# TEBF0808.net
KiCad netlist of a schematic drawn in Altium Designer
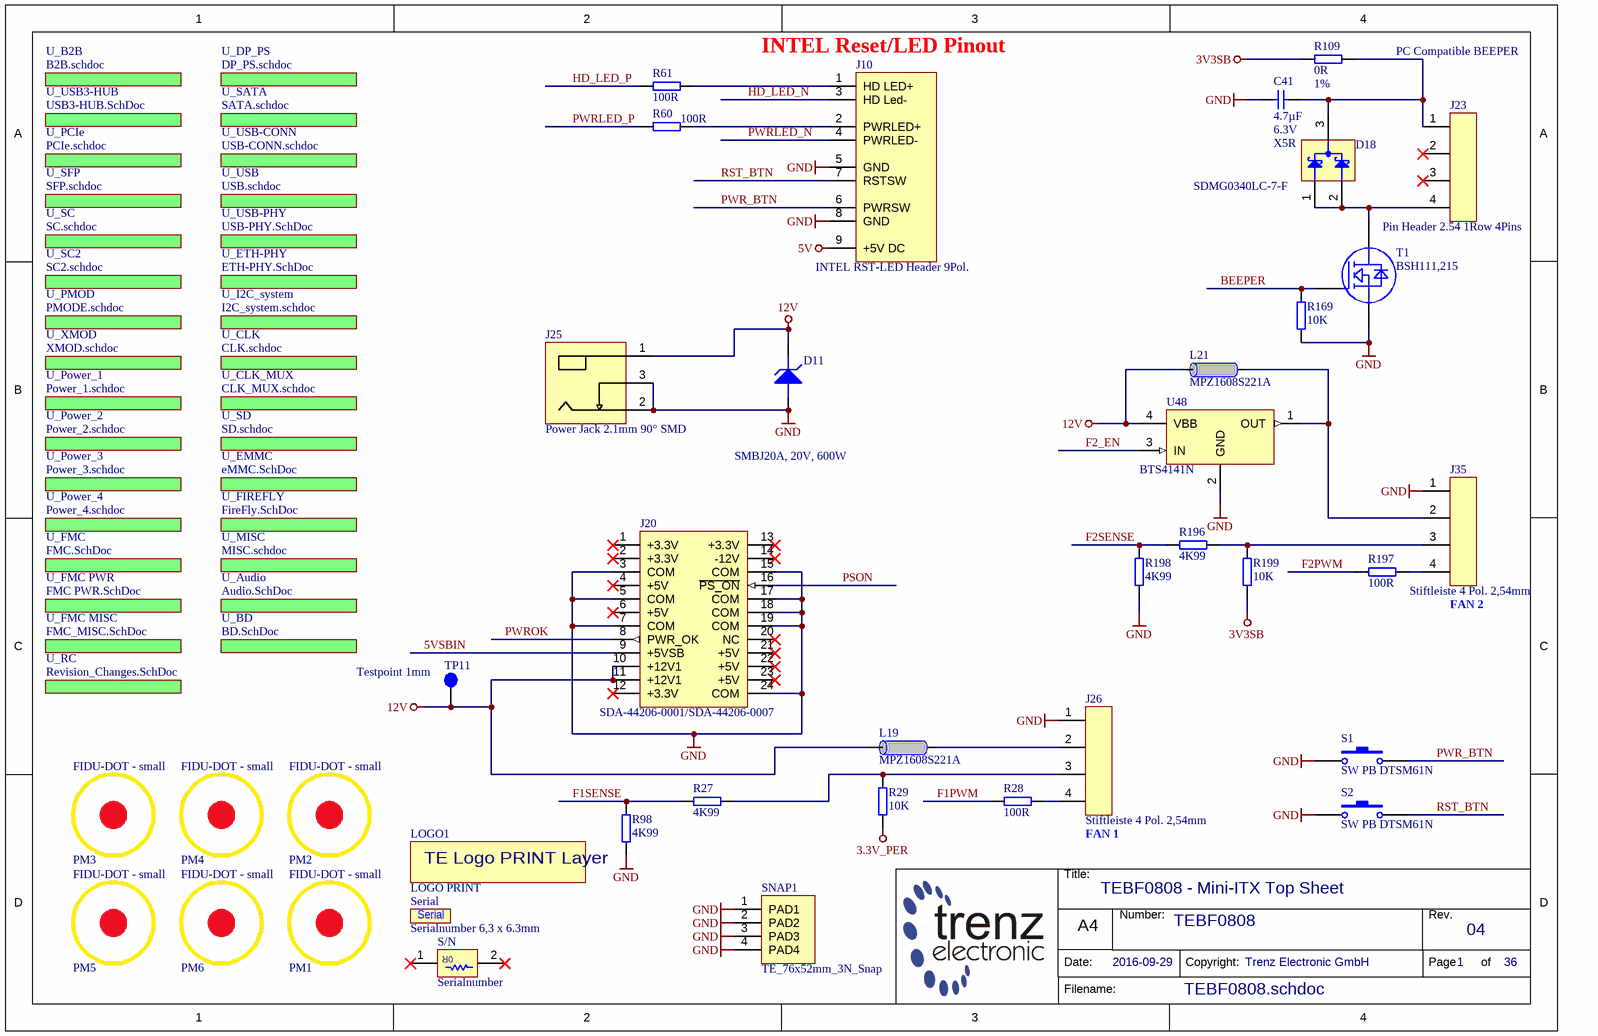
[diagram p0: TEBF0808.schdoc]

(export (version "E")
  (design (tool "Eeschema 10.0.6"))
  (components
    (comp (ref "C41")
      (value "4.7µF")
      (footprint "CAPC1005X60N")
      (description "KON 4.7µF 6.3V X5R SMD 20%")
      (fields
        (field (name "VOLTAGE") "6.3V")
        (field (name "TECHNOLOGY") "X5R")
        (field (name "TOLERANCE") "20%")
      )
      (libsource (lib "TE") (part "CAP-NP"))
    )
    (comp (ref "D11")
      (value "SMBJ20A, 20V, 600W")
      (footprint "DIOM5236X261N")
      (description "TVS, Unidirectional, 20V, 600W")
      (libsource (lib "TE") (part "SUPRESSOR"))
    )
    (comp (ref "D18")
      (value "SDMG0340LC-7-F")
      (footprint "SOT65P210X110-3N")
      (libsource (lib "TE") (part "SDMG0340LC"))
    )
    (comp (ref "J10")
      (value "INTEL RST-LED Header 9Pol.")
      (footprint "INTEL_FP_RST_LED_9PIN")
      (description "Stiftleiste Intel RST-LED Header 9polig")
      (libsource (lib "TE") (part "INTEL_FP_RST_LED_9PIN"))
    )
    (comp (ref "J20")
      (value "SDA-44206-0001/SDA-44206-0007")
      (footprint "SDA-44206-0001")
      (description "ATX Main Connector 24pol.")
      (libsource (lib "TE") (part "ATX-MAIN"))
    )
    (comp (ref "J23")
      (value "Pin Header 2.54 1Row 4Pins")
      (footprint "STIFTLEISTE2_54 OG 1R-4")
      (description "Stiftleiste gerade 1-reihig, 4pol.")
      (libsource (lib "TE") (part "CON-4"))
    )
    (comp (ref "J25")
      (value "Power Jack 2.1mm 90° SMD")
      (footprint "694106106102")
      (libsource (lib "TE") (part "694106106102"))
    )
    (comp (ref "J26")
      (value "Stiftleiste 4 Pol. 2,54mm")
      (footprint "47053-1000")
      (description "Stiftleiste 4 Pol. 7.5mm 2,54mm PC FAN")
      (libsource (lib "TE") (part "CON-4"))
    )
    (comp (ref "J35")
      (value "Stiftleiste 4 Pol. 2,54mm")
      (footprint "47053-1000")
      (description "Stiftleiste 4 Pol. 7.5mm 2,54mm PC FAN")
      (libsource (lib "TE") (part "CON-4"))
    )
    (comp (ref "L19")
      (value "MPZ1608S221A")
      (footprint "INDC1608X95N")
      (description "Ferritdurchführung MPZ1608S221A")
      (libsource (lib "TE") (part "Ferritperle"))
    )
    (comp (ref "L21")
      (value "MPZ1608S221A")
      (footprint "INDC1608X95N")
      (description "Ferritdurchführung MPZ1608S221A")
      (libsource (lib "TE") (part "Ferritperle"))
    )
    (comp (ref "LOGO1")
      (value "LOGO PRINT")
      (footprint "LOGO PRINT")
      (libsource (lib "TE") (part "LOGO PRINT"))
    )
    (comp (ref "PM1")
      (value "FIDU-DOT - small")
      (footprint "FIDU-DOT - small")
      (description "FIDU-DOT - SMALL 1mm")
      (libsource (lib "TE") (part "FIDU-DOT - small"))
    )
    (comp (ref "PM2")
      (value "FIDU-DOT - small")
      (footprint "FIDU-DOT - small")
      (description "FIDU-DOT - SMALL 1mm")
      (libsource (lib "TE") (part "FIDU-DOT - small"))
    )
    (comp (ref "PM3")
      (value "FIDU-DOT - small")
      (footprint "FIDU-DOT - small")
      (description "FIDU-DOT - SMALL 1mm")
      (libsource (lib "TE") (part "FIDU-DOT - small"))
    )
    (comp (ref "PM4")
      (value "FIDU-DOT - small")
      (footprint "FIDU-DOT - small")
      (description "FIDU-DOT - SMALL 1mm")
      (libsource (lib "TE") (part "FIDU-DOT - small"))
    )
    (comp (ref "PM5")
      (value "FIDU-DOT - small")
      (footprint "FIDU-DOT - small")
      (description "FIDU-DOT - SMALL 1mm")
      (libsource (lib "TE") (part "FIDU-DOT - small"))
    )
    (comp (ref "PM6")
      (value "FIDU-DOT - small")
      (footprint "FIDU-DOT - small")
      (description "FIDU-DOT - SMALL 1mm")
      (libsource (lib "TE") (part "FIDU-DOT - small"))
    )
    (comp (ref "R27")
      (value "4K99")
      (footprint "RESC1005X40N")
      (description "WID SMD 4K99 1% 0,063W")
      (fields (field (name "TOLERANCE") "1%"))
      (libsource (lib "TE") (part "RES"))
    )
    (comp (ref "R28")
      (value "100R")
      (footprint "RESC1005X40N")
      (description "WID SMD 100R 1% 0,063W")
      (fields (field (name "TOLERANCE") "1%"))
      (libsource (lib "TE") (part "RES"))
    )
    (comp (ref "R29")
      (value "10K")
      (footprint "RESC1005X40N")
      (description "WID SMD 10K 1% 0,063W")
      (fields (field (name "TOLERANCE") "1%"))
      (libsource (lib "TE") (part "RES"))
    )
    (comp (ref "R60")
      (value "100R")
      (footprint "RESC1005X40N")
      (description "WID SMD 100R 1% 0,063W")
      (fields (field (name "TOLERANCE") "1%"))
      (libsource (lib "TE") (part "RES"))
    )
    (comp (ref "R61")
      (value "100R")
      (footprint "RESC1005X40N")
      (description "WID SMD 100R 1% 0,063W")
      (fields (field (name "TOLERANCE") "1%"))
      (libsource (lib "TE") (part "RES"))
    )
    (comp (ref "R98")
      (value "4K99")
      (footprint "RESC1005X40N")
      (description "WID SMD 4K99 1% 0,063W")
      (fields (field (name "TOLERANCE") "1%"))
      (libsource (lib "TE") (part "RES"))
    )
    (comp (ref "R109")
      (value "0R")
      (footprint "RESC1005X40N")
      (description "WID SMD 0R")
      (fields (field (name "TOLERANCE") "1%"))
      (libsource (lib "TE") (part "RES"))
    )
    (comp (ref "R169")
      (value "10K")
      (footprint "RESC1005X40N")
      (description "WID SMD 10K 1% 0,063W")
      (fields (field (name "TOLERANCE") "1%"))
      (libsource (lib "TE") (part "RES"))
    )
    (comp (ref "R196")
      (value "4K99")
      (footprint "RESC1005X40N")
      (description "WID SMD 4K99 1% 0,063W")
      (fields (field (name "TOLERANCE") "1%"))
      (libsource (lib "TE") (part "RES"))
    )
    (comp (ref "R197")
      (value "100R")
      (footprint "RESC1005X40N")
      (description "WID SMD 100R 1% 0,063W")
      (fields (field (name "TOLERANCE") "1%"))
      (libsource (lib "TE") (part "RES"))
    )
    (comp (ref "R198")
      (value "4K99")
      (footprint "RESC1005X40N")
      (description "WID SMD 4K99 1% 0,063W")
      (fields (field (name "TOLERANCE") "1%"))
      (libsource (lib "TE") (part "RES"))
    )
    (comp (ref "R199")
      (value "10K")
      (footprint "RESC1005X40N")
      (description "WID SMD 10K 1% 0,063W")
      (fields (field (name "TOLERANCE") "1%"))
      (libsource (lib "TE") (part "RES"))
    )
    (comp (ref "S/N")
      (value "Serialnumber")
      (footprint "TraceabilityPad")
      (libsource (lib "TE") (part "TraceabilityPad"))
    )
    (comp (ref "S1")
      (value "SW PB DTSM61N")
      (footprint "DTSM61N")
      (description "Taster Miniatur Leiterplatte 1.6N")
      (libsource (lib "TE") (part "SW PB DTSM61N"))
    )
    (comp (ref "S2")
      (value "SW PB DTSM61N")
      (footprint "DTSM61N")
      (description "Taster Miniatur Leiterplatte 1.6N")
      (libsource (lib "TE") (part "SW PB DTSM61N"))
    )
    (comp (ref "Serial")
      (value "Serialnumber 6,3 x 6.3mm")
      (footprint "Serial_6.3x6.3mm")
      (libsource (lib "TE") (part "Serial"))
    )
    (comp (ref "SNAP1")
      (value "TE_76x52mm_3N_Snap")
      (footprint "TE_76x52mm_Snap")
      (description "TE0808 76x52mm Snap")
      (libsource (lib "TE") (part "TE_50x40mm_Snap"))
    )
    (comp (ref "T1")
      (value "BSH111,215")
      (footprint "SOT95P230X109-3N")
      (libsource (lib "TE") (part "BSH103"))
    )
    (comp (ref "TP11") (value "Testpoint 1mm") (footprint "TP_1mm") (libsource (lib "TE") (part "TP")))
    (comp (ref "U48")
      (value "BTS4141N")
      (footprint "SOT230P700X180-4N")
      (libsource (lib "TE") (part "BTS4141N"))
    )
  )
  (nets
    (net (code "1") (name "/5VSBIN") (class "Default")
      (node (ref "J20") (pin "9") (pinfunction "+5VSB_9") (pintype "power_in"))
    )
    (net (code "2") (name "/BEEPER") (class "Default")
      (node (ref "R169") (pin "2") (pinfunction "2_2") (pintype "passive"))
      (node (ref "T1") (pin "1") (pinfunction "GATE_1") (pintype "passive"))
    )
    (net (code "3") (name "/F1PWM") (class "Default")
      (node (ref "R28") (pin "1") (pinfunction "1_1") (pintype "passive"))
    )
    (net (code "4") (name "/F1SENSE") (class "Default")
      (node (ref "R27") (pin "1") (pinfunction "1_1") (pintype "passive"))
      (node (ref "R98") (pin "1") (pinfunction "1_1") (pintype "passive"))
    )
    (net (code "5") (name "/F2PWM") (class "Default")
      (node (ref "R197") (pin "1") (pinfunction "1_1") (pintype "passive"))
    )
    (net (code "6") (name "/F2SENSE") (class "Default")
      (node (ref "R196") (pin "1") (pinfunction "1_1") (pintype "passive"))
      (node (ref "R198") (pin "1") (pinfunction "1_1") (pintype "passive"))
    )
    (net (code "7") (name "/F2_EN") (class "Default")
      (node (ref "U48") (pin "3") (pinfunction "IN_3") (pintype "input"))
    )
    (net (code "8") (name "/HD_LED_N") (class "Default")
      (node (ref "J10") (pin "3") (pinfunction "HD_Led-_3") (pintype "passive"))
    )
    (net (code "9") (name "/HD_LED_P") (class "Default")
      (node (ref "R61") (pin "1") (pinfunction "1_1") (pintype "passive"))
    )
    (net (code "10") (name "/PSON") (class "Default")
      (node (ref "J20") (pin "16") (pinfunction "~{PS_ON}_16") (pintype "input"))
    )
    (net (code "11") (name "/PWRLED_N") (class "Default")
      (node (ref "J10") (pin "4") (pinfunction "PWRLED-_4") (pintype "passive"))
    )
    (net (code "12") (name "/PWRLED_P") (class "Default")
      (node (ref "R60") (pin "1") (pinfunction "1_1") (pintype "passive"))
    )
    (net (code "13") (name "/PWROK") (class "Default")
      (node (ref "J20") (pin "8") (pinfunction "PWR_OK_8") (pintype "output"))
    )
    (net (code "14") (name "/PWR_BTN") (class "Default")
      (node (ref "J10") (pin "6") (pinfunction "PWRSW_6") (pintype "passive"))
      (node (ref "S1") (pin "2") (pinfunction "2_2") (pintype "passive"))
    )
    (net (code "15") (name "/RST_BTN") (class "Default")
      (node (ref "J10") (pin "7") (pinfunction "RSTSW_7") (pintype "passive"))
      (node (ref "S2") (pin "2") (pinfunction "2_2") (pintype "passive"))
    )
    (net (code "16") (name "3.3V_PER") (class "Default")
      (node (ref "R29") (pin "2") (pinfunction "2_2") (pintype "passive"))
    )
    (net (code "17") (name "3V3SB") (class "Default")
      (node (ref "R109") (pin "1") (pinfunction "1_1") (pintype "passive"))
      (node (ref "R199") (pin "2") (pinfunction "2_2") (pintype "passive"))
    )
    (net (code "18") (name "5V") (class "Default")
      (node (ref "J10") (pin "9") (pinfunction "+5V_DC_9") (pintype "passive"))
    )
    (net (code "19") (name "12V") (class "Default")
      (node (ref "D11") (pin "1") (pinfunction "KATHODE_1") (pintype "passive"))
      (node (ref "J20") (pin "10") (pinfunction "+12V1_10") (pintype "power_in"))
      (node (ref "J20") (pin "11") (pinfunction "+12V1_11") (pintype "power_in"))
      (node (ref "J25") (pin "1") (pintype "passive"))
      (node (ref "L19") (pin "2") (pinfunction "2_2") (pintype "passive"))
      (node (ref "L21") (pin "2") (pinfunction "2_2") (pintype "passive"))
      (node (ref "TP11") (pin "1") (pintype "passive"))
      (node (ref "U48") (pin "4") (pinfunction "VBB_4") (pintype "power_in"))
    )
    (net (code "20") (name "GND") (class "Default")
      (node (ref "C41") (pin "1") (pinfunction "1_1") (pintype "passive"))
      (node (ref "D11") (pin "2") (pinfunction "ANODE_2") (pintype "passive"))
      (node (ref "J10") (pin "5") (pinfunction "GND_5") (pintype "passive"))
      (node (ref "J10") (pin "8") (pinfunction "GND_8") (pintype "passive"))
      (node (ref "J20") (pin "15") (pinfunction "COM_15") (pintype "power_in"))
      (node (ref "J20") (pin "17") (pinfunction "COM_17") (pintype "power_in"))
      (node (ref "J20") (pin "18") (pinfunction "COM_18") (pintype "power_in"))
      (node (ref "J20") (pin "19") (pinfunction "COM_19") (pintype "power_in"))
      (node (ref "J20") (pin "24") (pinfunction "COM_24") (pintype "power_in"))
      (node (ref "J20") (pin "3") (pinfunction "COM_3") (pintype "power_in"))
      (node (ref "J20") (pin "5") (pinfunction "COM_5") (pintype "power_in"))
      (node (ref "J20") (pin "7") (pinfunction "COM_7") (pintype "power_in"))
      (node (ref "J25") (pin "2") (pintype "passive"))
      (node (ref "J25") (pin "3") (pintype "passive"))
      (node (ref "J26") (pin "1") (pintype "passive"))
      (node (ref "J35") (pin "1") (pintype "passive"))
      (node (ref "R169") (pin "1") (pinfunction "1_1") (pintype "passive"))
      (node (ref "R198") (pin "2") (pinfunction "2_2") (pintype "passive"))
      (node (ref "R98") (pin "2") (pinfunction "2_2") (pintype "passive"))
      (node (ref "S1") (pin "1") (pinfunction "1_1") (pintype "passive"))
      (node (ref "S2") (pin "1") (pinfunction "1_1") (pintype "passive"))
      (node (ref "SNAP1") (pin "1") (pinfunction "PAD1_1") (pintype "power_in"))
      (node (ref "SNAP1") (pin "2") (pinfunction "PAD2_2") (pintype "power_in"))
      (node (ref "SNAP1") (pin "3") (pinfunction "PAD3_3") (pintype "power_in"))
      (node (ref "SNAP1") (pin "4") (pinfunction "PAD4_4") (pintype "power_in"))
      (node (ref "T1") (pin "2") (pinfunction "SOURCE_2") (pintype "passive"))
      (node (ref "U48") (pin "2") (pinfunction "GND_2") (pintype "power_in"))
    )
    (net (code "21") (name "Net-(D18-K)") (class "Default")
      (node (ref "C41") (pin "2") (pinfunction "2_2") (pintype "passive"))
      (node (ref "D18") (pin "3") (pinfunction "K_3") (pintype "passive"))
      (node (ref "J23") (pin "1") (pintype "passive"))
      (node (ref "R109") (pin "2") (pinfunction "2_2") (pintype "passive"))
    )
    (net (code "22") (name "Net-(J10-HD_LED+)") (class "Default")
      (node (ref "J10") (pin "1") (pinfunction "HD_LED+_1") (pintype "passive"))
      (node (ref "R61") (pin "2") (pinfunction "2_2") (pintype "passive"))
    )
    (net (code "23") (name "Net-(J10-PWRLED+)") (class "Default")
      (node (ref "J10") (pin "2") (pinfunction "PWRLED+_2") (pintype "passive"))
      (node (ref "R60") (pin "2") (pinfunction "2_2") (pintype "passive"))
    )
    (net (code "24") (name "Net-(J26-Pad2)") (class "Default")
      (node (ref "J26") (pin "2") (pintype "passive"))
      (node (ref "L19") (pin "1") (pinfunction "1_1") (pintype "passive"))
    )
    (net (code "25") (name "Net-(J26-Pad3)") (class "Default")
      (node (ref "J26") (pin "3") (pintype "passive"))
      (node (ref "R27") (pin "2") (pinfunction "2_2") (pintype "passive"))
      (node (ref "R29") (pin "1") (pinfunction "1_1") (pintype "passive"))
    )
    (net (code "26") (name "Net-(J26-Pad4)") (class "Default")
      (node (ref "J26") (pin "4") (pintype "passive"))
      (node (ref "R28") (pin "2") (pinfunction "2_2") (pintype "passive"))
    )
    (net (code "27") (name "Net-(J35-Pad3)") (class "Default")
      (node (ref "J35") (pin "3") (pintype "passive"))
      (node (ref "R196") (pin "2") (pinfunction "2_2") (pintype "passive"))
      (node (ref "R199") (pin "1") (pinfunction "1_1") (pintype "passive"))
    )
    (net (code "28") (name "Net-(J35-Pad4)") (class "Default")
      (node (ref "J35") (pin "4") (pintype "passive"))
      (node (ref "R197") (pin "2") (pinfunction "2_2") (pintype "passive"))
    )
    (net (code "29") (name "Net-(T1-DRAIN)") (class "Default")
      (node (ref "D18") (pin "1") (pinfunction "A_1") (pintype "passive"))
      (node (ref "D18") (pin "2") (pinfunction "A_2") (pintype "passive"))
      (node (ref "J23") (pin "4") (pintype "passive"))
      (node (ref "T1") (pin "3") (pinfunction "DRAIN_3") (pintype "passive"))
    )
    (net (code "30") (name "Net-(U48-OUT)") (class "Default")
      (node (ref "J35") (pin "2") (pintype "passive"))
      (node (ref "L21") (pin "1") (pinfunction "1_1") (pintype "passive"))
      (node (ref "U48") (pin "1") (pinfunction "OUT_1") (pintype "output"))
    )
    (net (code "31") (name "unconnected-(J20-+3.3V-Pad1)") (class "Default")
      (node (ref "J20") (pin "1") (pinfunction "+3.3V_1") (pintype "power_in+no_connect"))
    )
    (net (code "32") (name "unconnected-(J20-+3.3V-Pad2)") (class "Default")
      (node (ref "J20") (pin "2") (pinfunction "+3.3V_2") (pintype "power_in+no_connect"))
    )
    (net (code "33") (name "unconnected-(J20-+3.3V-Pad12)") (class "Default")
      (node (ref "J20") (pin "12") (pinfunction "+3.3V_12") (pintype "power_in+no_connect"))
    )
    (net (code "34") (name "unconnected-(J20-+3.3V-Pad13)") (class "Default")
      (node (ref "J20") (pin "13") (pinfunction "+3.3V_13") (pintype "power_in+no_connect"))
    )
    (net (code "35") (name "unconnected-(J20-+5V-Pad4)") (class "Default")
      (node (ref "J20") (pin "4") (pinfunction "+5V_4") (pintype "power_in+no_connect"))
    )
    (net (code "36") (name "unconnected-(J20-+5V-Pad6)") (class "Default")
      (node (ref "J20") (pin "6") (pinfunction "+5V_6") (pintype "power_in+no_connect"))
    )
    (net (code "37") (name "unconnected-(J20-+5V-Pad21)") (class "Default")
      (node (ref "J20") (pin "21") (pinfunction "+5V_21") (pintype "power_in+no_connect"))
    )
    (net (code "38") (name "unconnected-(J20-+5V-Pad22)") (class "Default")
      (node (ref "J20") (pin "22") (pinfunction "+5V_22") (pintype "power_in+no_connect"))
    )
    (net (code "39") (name "unconnected-(J20-+5V-Pad23)") (class "Default")
      (node (ref "J20") (pin "23") (pinfunction "+5V_23") (pintype "power_in+no_connect"))
    )
    (net (code "40") (name "unconnected-(J20--12V-Pad14)") (class "Default")
      (node (ref "J20") (pin "14") (pinfunction "-12V_14") (pintype "power_in+no_connect"))
    )
    (net (code "41") (name "unconnected-(J20-NC-Pad20)") (class "Default")
      (node (ref "J20") (pin "20") (pinfunction "NC_20") (pintype "passive+no_connect"))
    )
    (net (code "42") (name "unconnected-(J23-Pad2)") (class "Default")
      (node (ref "J23") (pin "2") (pintype "passive+no_connect"))
    )
    (net (code "43") (name "unconnected-(J23-Pad3)") (class "Default")
      (node (ref "J23") (pin "3") (pintype "passive+no_connect"))
    )
    (net (code "44") (name "unconnected-(S/N-Pad1)") (class "Default")
      (node (ref "S/N") (pin "1") (pintype "passive+no_connect"))
    )
    (net (code "45") (name "unconnected-(S/N-Pad2)") (class "Default")
      (node (ref "S/N") (pin "2") (pintype "passive+no_connect"))
    )
  )
)
